# Reefing-MCU.net
KiCad netlist of a schematic drawn in Altium Designer
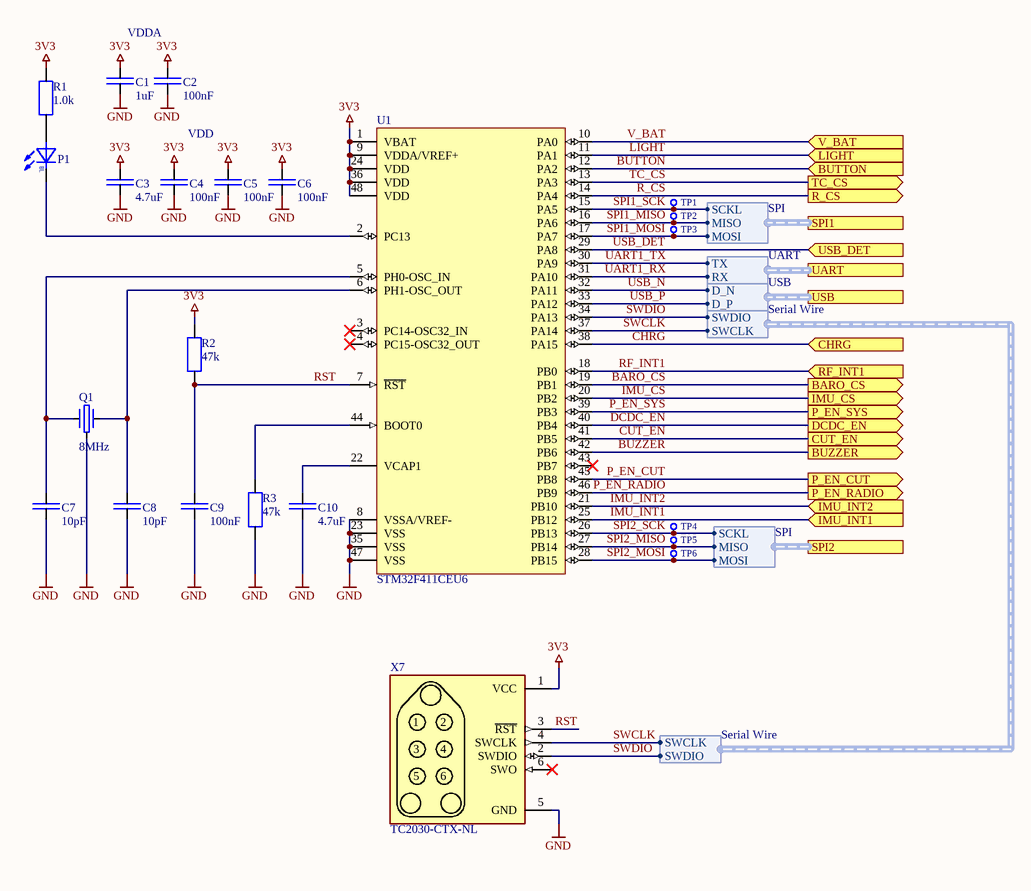
[diagram p0: Reefing-MCU.SchDoc]

(export (version "E")
  (design (tool "Eeschema 10.0.6"))
  (components
    (comp (ref "C1")
      (value "1uF")
      (footprint "SMD Keramikkondensator 0402")
      (description "SMD Ceramic Capacitor E6")
      (libsource (lib "CATS-EUROC") (part "E6 - 1uF"))
    )
    (comp (ref "C2")
      (value "100nF")
      (footprint "SMD Keramikkondensator 0402")
      (description "SMD Ceramic Capacitor E6")
      (libsource (lib "CATS-EUROC") (part "E6 - 100nF"))
    )
    (comp (ref "C3")
      (value "4.7uF")
      (footprint "SMD Keramikkondensator 0402")
      (description "SMD Ceramic Capacitor E6")
      (libsource (lib "CATS-EUROC") (part "E6 - 4.7uF"))
    )
    (comp (ref "C4")
      (value "100nF")
      (footprint "SMD Keramikkondensator 0402")
      (description "SMD Ceramic Capacitor E6")
      (libsource (lib "CATS-EUROC") (part "E6 - 100nF"))
    )
    (comp (ref "C5")
      (value "100nF")
      (footprint "SMD Keramikkondensator 0402")
      (description "SMD Ceramic Capacitor E6")
      (libsource (lib "CATS-EUROC") (part "E6 - 100nF"))
    )
    (comp (ref "C6")
      (value "100nF")
      (footprint "SMD Keramikkondensator 0402")
      (description "SMD Ceramic Capacitor E6")
      (libsource (lib "CATS-EUROC") (part "E6 - 100nF"))
    )
    (comp (ref "C7")
      (value "10pF")
      (footprint "SMD Keramikkondensator 0402")
      (description "SMD Ceramic Capacitor E6")
      (libsource (lib "CATS-EUROC") (part "E6 - 10pF"))
    )
    (comp (ref "C8")
      (value "10pF")
      (footprint "SMD Keramikkondensator 0402")
      (description "SMD Ceramic Capacitor E6")
      (libsource (lib "CATS-EUROC") (part "E6 - 10pF"))
    )
    (comp (ref "C9")
      (value "100nF")
      (footprint "SMD Keramikkondensator 0402")
      (description "SMD Ceramic Capacitor E6")
      (libsource (lib "CATS-EUROC") (part "E6 - 100nF"))
    )
    (comp (ref "C10")
      (value "4.7uF")
      (footprint "SMD Keramikkondensator 0402")
      (description "SMD Ceramic Capacitor E6")
      (libsource (lib "CATS-EUROC") (part "E6 - 4.7uF"))
    )
    (comp (ref "P1")
      (value "LED")
      (footprint "SMD LED 0603")
      (description "Color LED")
      (libsource (lib "Diodes") (part "LED"))
    )
    (comp (ref "Q1")
      (value "8MHz")
      (footprint "SMD Crystal 3.2X2.5X0.8")
      (description "SMD Crystal Resonators 8MHz ±10ppm SMD,3.2x2.5mm")
      (libsource (lib "Other") (part "Crystal"))
    )
    (comp (ref "R1")
      (value "1.0k")
      (footprint "SMD Widerstand 0402")
      (description "SMD Chip Resistor E24")
      (libsource (lib "CATS-EUROC") (part "E24 - 1.0k"))
    )
    (comp (ref "R2")
      (value "47k")
      (footprint "SMD Widerstand 0402")
      (description "SMD Chip Resistor E24")
      (libsource (lib "Resistors-E24") (part "E24 - 47k"))
    )
    (comp (ref "R3")
      (value "47k")
      (footprint "SMD Widerstand 0402")
      (description "SMD Chip Resistor E24")
      (libsource (lib "Resistors-E24") (part "E24 - 47k"))
    )
    (comp (ref "TP1")
      (value "X-TP")
      (footprint "SMD Testpoint 1mm")
      (description "Testpunkt")
      (libsource (lib "Fleet-Monitor") (part "X-TP"))
    )
    (comp (ref "TP2")
      (value "X-TP")
      (footprint "SMD Testpoint 1mm")
      (description "Testpunkt")
      (libsource (lib "Fleet-Monitor") (part "X-TP"))
    )
    (comp (ref "TP3")
      (value "X-TP")
      (footprint "SMD Testpoint 1mm")
      (description "Testpunkt")
      (libsource (lib "Fleet-Monitor") (part "X-TP"))
    )
    (comp (ref "TP4")
      (value "X-TP")
      (footprint "SMD Testpoint 1mm")
      (description "Testpunkt")
      (libsource (lib "Fleet-Monitor") (part "X-TP"))
    )
    (comp (ref "TP5")
      (value "X-TP")
      (footprint "SMD Testpoint 1mm")
      (description "Testpunkt")
      (libsource (lib "Fleet-Monitor") (part "X-TP"))
    )
    (comp (ref "TP6")
      (value "X-TP")
      (footprint "SMD Testpoint 1mm")
      (description "Testpunkt")
      (libsource (lib "Fleet-Monitor") (part "X-TP"))
    )
    (comp (ref "U1")
      (value "STM32F411CEU6")
      (footprint "SMD IC QFN-48")
      (description "ARM® Cortex®-M4 series Microcontroller IC 32-Bit 100MHz 512KB (512K x 8) FLASH 48-UFQFPN (7x7)")
      (libsource (lib "Microcontrollers") (part "STM32F411CEU6"))
    )
    (comp (ref "X7")
      (value "TC2030-CTX-NL")
      (footprint "SMD Connector TC2030")
      (description "Tag-Connect for ARM-Cortex (6-Pin)")
      (libsource (lib "Connectors") (part "TC2030-CTX-NL"))
    )
  )
  (nets
    (net (code "6") (name "/BARO_CS") (class "Default")
      (node (ref "U1") (pin "19") (pinfunction "PB1_19") (pintype "bidirectional"))
    )
    (net (code "7") (name "/BUTTON") (class "Default")
      (node (ref "U1") (pin "12") (pinfunction "PA2_12") (pintype "bidirectional"))
    )
    (net (code "8") (name "/BUZZER") (class "Default")
      (node (ref "U1") (pin "42") (pinfunction "PB6_42") (pintype "bidirectional"))
    )
    (net (code "9") (name "/CHRG") (class "Default")
      (node (ref "U1") (pin "38") (pinfunction "PA15_38") (pintype "bidirectional"))
    )
    (net (code "10") (name "/CUT_EN") (class "Default")
      (node (ref "U1") (pin "41") (pinfunction "PB5_41") (pintype "bidirectional"))
    )
    (net (code "11") (name "/DCDC_EN") (class "Default")
      (node (ref "U1") (pin "40") (pinfunction "PB4_40") (pintype "bidirectional"))
    )
    (net (code "12") (name "/IMU_CS") (class "Default")
      (node (ref "U1") (pin "20") (pinfunction "PB2_20") (pintype "bidirectional"))
    )
    (net (code "13") (name "/IMU_INT1") (class "Default")
      (node (ref "U1") (pin "25") (pinfunction "PB12_25") (pintype "bidirectional"))
    )
    (net (code "14") (name "/IMU_INT2") (class "Default")
      (node (ref "U1") (pin "21") (pinfunction "PB10_21") (pintype "bidirectional"))
    )
    (net (code "15") (name "/LIGHT") (class "Default")
      (node (ref "U1") (pin "11") (pinfunction "PA1_11") (pintype "bidirectional"))
    )
    (net (code "16") (name "/P_EN_CUT") (class "Default")
      (node (ref "U1") (pin "45") (pinfunction "PB8_45") (pintype "bidirectional"))
    )
    (net (code "17") (name "/P_EN_RADIO") (class "Default")
      (node (ref "U1") (pin "46") (pinfunction "PB9_46") (pintype "bidirectional"))
    )
    (net (code "18") (name "/P_EN_SYS") (class "Default")
      (node (ref "U1") (pin "39") (pinfunction "PB3_39") (pintype "bidirectional"))
    )
    (net (code "19") (name "/RF_INT1") (class "Default")
      (node (ref "U1") (pin "18") (pinfunction "PB0_18") (pintype "bidirectional"))
    )
    (net (code "20") (name "/RST") (class "Default")
      (node (ref "C9") (pin "2") (pinfunction "2_2") (pintype "passive"))
      (node (ref "R2") (pin "1") (pinfunction "1_1") (pintype "passive"))
      (node (ref "U1") (pin "7") (pinfunction "~{RST}_7") (pintype "input"))
      (node (ref "X7") (pin "3") (pinfunction "~{RST}_3") (pintype "output"))
    )
    (net (code "21") (name "/R_CS") (class "Default")
      (node (ref "U1") (pin "14") (pinfunction "PA4_14") (pintype "bidirectional"))
    )
    (net (code "22") (name "/SPI1_MISO") (class "Default")
      (node (ref "TP2") (pin "1") (pinfunction "1_1") (pintype "passive"))
      (node (ref "U1") (pin "16") (pinfunction "PA6_16") (pintype "bidirectional"))
    )
    (net (code "23") (name "/SPI1_MOSI") (class "Default")
      (node (ref "TP3") (pin "1") (pinfunction "1_1") (pintype "passive"))
      (node (ref "U1") (pin "17") (pinfunction "PA7_17") (pintype "bidirectional"))
    )
    (net (code "24") (name "/SPI1_SCK") (class "Default")
      (node (ref "TP1") (pin "1") (pinfunction "1_1") (pintype "passive"))
      (node (ref "U1") (pin "15") (pinfunction "PA5_15") (pintype "bidirectional"))
    )
    (net (code "25") (name "/SPI2_MISO") (class "Default")
      (node (ref "TP5") (pin "1") (pinfunction "1_1") (pintype "passive"))
      (node (ref "U1") (pin "27") (pinfunction "PB14_27") (pintype "bidirectional"))
    )
    (net (code "26") (name "/SPI2_MOSI") (class "Default")
      (node (ref "TP6") (pin "1") (pinfunction "1_1") (pintype "passive"))
      (node (ref "U1") (pin "28") (pinfunction "PB15_28") (pintype "bidirectional"))
    )
    (net (code "27") (name "/SPI2_SCK") (class "Default")
      (node (ref "TP4") (pin "1") (pinfunction "1_1") (pintype "passive"))
      (node (ref "U1") (pin "26") (pinfunction "PB13_26") (pintype "bidirectional"))
    )
    (net (code "28") (name "/SWCLK") (class "Default")
      (node (ref "U1") (pin "37") (pinfunction "PA14_37") (pintype "bidirectional"))
      (node (ref "X7") (pin "4") (pinfunction "SWCLK_4") (pintype "output"))
    )
    (net (code "29") (name "/SWDIO") (class "Default")
      (node (ref "U1") (pin "34") (pinfunction "PA13_34") (pintype "bidirectional"))
      (node (ref "X7") (pin "2") (pinfunction "SWDIO_2") (pintype "bidirectional"))
    )
    (net (code "30") (name "/TC_CS") (class "Default")
      (node (ref "U1") (pin "13") (pinfunction "PA3_13") (pintype "bidirectional"))
    )
    (net (code "31") (name "/UART1_RX") (class "Default")
      (node (ref "U1") (pin "31") (pinfunction "PA10_31") (pintype "bidirectional"))
    )
    (net (code "32") (name "/UART1_TX") (class "Default")
      (node (ref "U1") (pin "30") (pinfunction "PA9_30") (pintype "bidirectional"))
    )
    (net (code "33") (name "/USB_DET") (class "Default")
      (node (ref "U1") (pin "29") (pinfunction "PA8_29") (pintype "bidirectional"))
    )
    (net (code "34") (name "/USB_N") (class "Default")
      (node (ref "U1") (pin "32") (pinfunction "PA11_32") (pintype "bidirectional"))
    )
    (net (code "35") (name "/USB_P") (class "Default")
      (node (ref "U1") (pin "33") (pinfunction "PA12_33") (pintype "bidirectional"))
    )
    (net (code "36") (name "/V_BAT") (class "Default")
      (node (ref "U1") (pin "10") (pinfunction "PA0_10") (pintype "bidirectional"))
    )
    (net (code "41") (name "3V3") (class "Default")
      (node (ref "C1") (pin "2") (pinfunction "2_2") (pintype "passive"))
      (node (ref "C2") (pin "2") (pinfunction "2_2") (pintype "passive"))
      (node (ref "C3") (pin "2") (pinfunction "2_2") (pintype "passive"))
      (node (ref "C4") (pin "2") (pinfunction "2_2") (pintype "passive"))
      (node (ref "C5") (pin "2") (pinfunction "2_2") (pintype "passive"))
      (node (ref "C6") (pin "2") (pinfunction "2_2") (pintype "passive"))
      (node (ref "R1") (pin "2") (pinfunction "2_2") (pintype "passive"))
      (node (ref "R2") (pin "2") (pinfunction "2_2") (pintype "passive"))
      (node (ref "U1") (pin "1") (pinfunction "VBAT_1") (pintype "passive"))
      (node (ref "U1") (pin "24") (pinfunction "VDD_24") (pintype "passive"))
      (node (ref "U1") (pin "36") (pinfunction "VDD_36") (pintype "passive"))
      (node (ref "U1") (pin "48") (pinfunction "VDD_48") (pintype "passive"))
      (node (ref "U1") (pin "9") (pinfunction "VDDA/VREF+_9") (pintype "passive"))
      (node (ref "X7") (pin "1") (pinfunction "VCC_1") (pintype "power_in"))
    )
    (net (code "42") (name "GND") (class "Default")
      (node (ref "C1") (pin "1") (pinfunction "1_1") (pintype "passive"))
      (node (ref "C10") (pin "1") (pinfunction "1_1") (pintype "passive"))
      (node (ref "C2") (pin "1") (pinfunction "1_1") (pintype "passive"))
      (node (ref "C3") (pin "1") (pinfunction "1_1") (pintype "passive"))
      (node (ref "C4") (pin "1") (pinfunction "1_1") (pintype "passive"))
      (node (ref "C5") (pin "1") (pinfunction "1_1") (pintype "passive"))
      (node (ref "C6") (pin "1") (pinfunction "1_1") (pintype "passive"))
      (node (ref "C7") (pin "1") (pinfunction "1_1") (pintype "passive"))
      (node (ref "C8") (pin "1") (pinfunction "1_1") (pintype "passive"))
      (node (ref "C9") (pin "1") (pinfunction "1_1") (pintype "passive"))
      (node (ref "Q1") (pin "3") (pinfunction "3_3") (pintype "power_in"))
      (node (ref "R3") (pin "1") (pinfunction "1_1") (pintype "passive"))
      (node (ref "U1") (pin "23") (pinfunction "VSS_23") (pintype "passive"))
      (node (ref "U1") (pin "35") (pinfunction "VSS_35") (pintype "passive"))
      (node (ref "U1") (pin "47") (pinfunction "VSS_47") (pintype "passive"))
      (node (ref "U1") (pin "8") (pinfunction "VSSA/VREF-_8") (pintype "passive"))
      (node (ref "X7") (pin "5") (pinfunction "GND_5") (pintype "power_in"))
    )
    (net (code "43") (name "Net-(P1-PadA)") (class "Default")
      (node (ref "P1") (pin "A") (pinfunction "A_A") (pintype "passive"))
      (node (ref "R1") (pin "1") (pinfunction "1_1") (pintype "passive"))
    )
    (net (code "44") (name "Net-(U1-BOOT0)") (class "Default")
      (node (ref "R3") (pin "2") (pinfunction "2_2") (pintype "passive"))
      (node (ref "U1") (pin "44") (pinfunction "BOOT0_44") (pintype "input"))
    )
    (net (code "45") (name "Net-(U1-PC13)") (class "Default")
      (node (ref "P1") (pin "K") (pinfunction "K_K") (pintype "passive"))
      (node (ref "U1") (pin "2") (pinfunction "PC13_2") (pintype "bidirectional"))
    )
    (net (code "46") (name "Net-(U1-PH0-OSC_IN)") (class "Default")
      (node (ref "C7") (pin "2") (pinfunction "2_2") (pintype "passive"))
      (node (ref "Q1") (pin "1") (pinfunction "1_1") (pintype "passive"))
      (node (ref "U1") (pin "5") (pinfunction "PH0-OSC_IN_5") (pintype "bidirectional"))
    )
    (net (code "47") (name "Net-(U1-PH1-OSC_OUT)") (class "Default")
      (node (ref "C8") (pin "2") (pinfunction "2_2") (pintype "passive"))
      (node (ref "Q1") (pin "2") (pinfunction "2_2") (pintype "passive"))
      (node (ref "U1") (pin "6") (pinfunction "PH1-OSC_OUT_6") (pintype "bidirectional"))
    )
    (net (code "48") (name "Net-(U1-VCAP1)") (class "Default")
      (node (ref "C10") (pin "2") (pinfunction "2_2") (pintype "passive"))
      (node (ref "U1") (pin "22") (pinfunction "VCAP1_22") (pintype "passive"))
    )
    (net (code "49") (name "unconnected-(U1-PB7-Pad43)") (class "Default")
      (node (ref "U1") (pin "43") (pinfunction "PB7_43") (pintype "bidirectional+no_connect"))
    )
    (net (code "50") (name "unconnected-(U1-PC14-OSC32_IN-Pad3)") (class "Default")
      (node (ref "U1") (pin "3") (pinfunction "PC14-OSC32_IN_3") (pintype "bidirectional+no_connect"))
    )
    (net (code "51") (name "unconnected-(U1-PC15-OSC32_OUT-Pad4)") (class "Default")
      (node (ref "U1") (pin "4") (pinfunction "PC15-OSC32_OUT_4") (pintype "bidirectional+no_connect"))
    )
    (net (code "52") (name "unconnected-(X7-SWO-Pad6)") (class "Default")
      (node (ref "X7") (pin "6") (pinfunction "SWO_6") (pintype "input+no_connect"))
    )
  )
)
